# MCU.net
KiCad netlist of a schematic drawn in Altium Designer
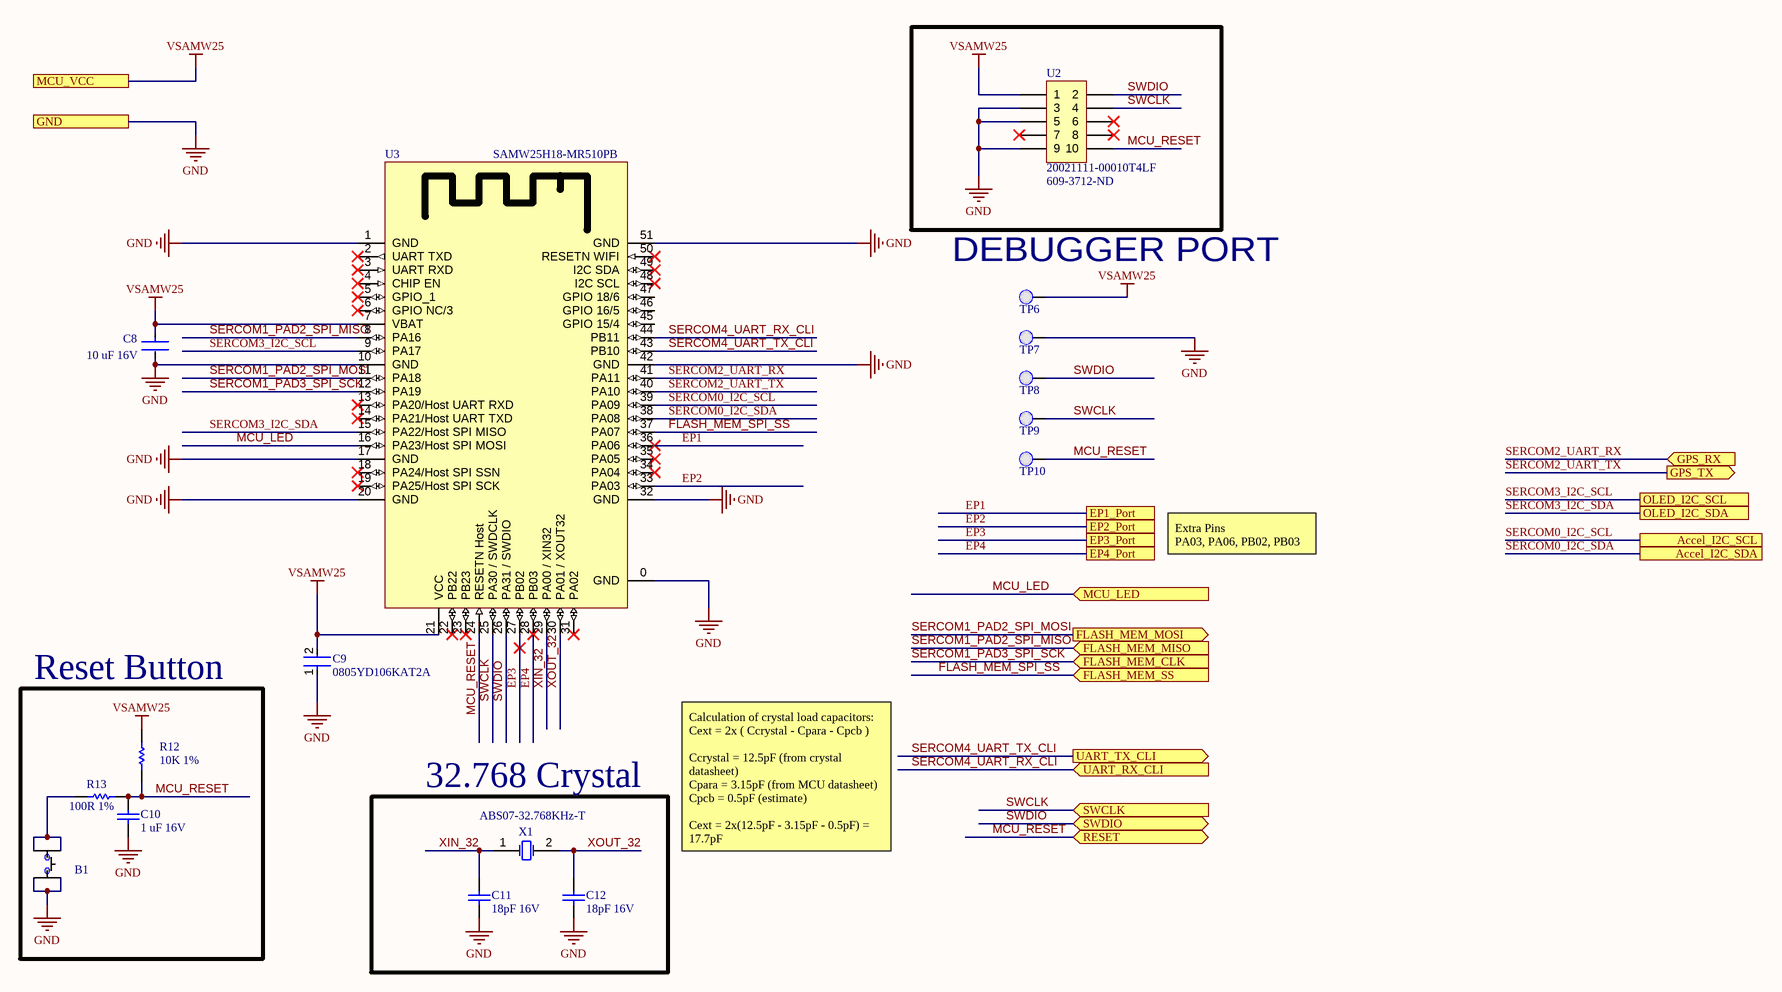
[diagram p0: MCU.SchDoc]

(export (version "E")
  (design (tool "Eeschema 10.0.6"))
  (components
    (comp (ref "B1")
      (value "PTS810 SJK 250 SMTR LFS")
      (footprint "PTS810 SJK 250 SMTR LFS")
      (description "SWITCH TACTILE SPST-NO 0.05A 16V Tactile Switch SPST-NO Top Actuated Surface Mount")
      (fields
        (field (name "MANUFACTURER") "ITT /  C&K Components")
        (field (name "MANUFACTURER PART NUMBER") "PTS810SJK250SMTRLFS")
      )
      (libsource (lib "Schematics") (part "PTS810 SJK 250 SMTR LFS"))
    )
    (comp (ref "C8")
      (value "10 uF 16V")
      (footprint "FP-0805-L_2_01_0_2-W_1_25-MFG")
      (description "General Purpose Ceramic Capacitor, 0805, 10uF, 10%, X5R, 15%, 16V")
      (fields (field (name "TOLERANCE") "10%") (field (name "VOLTAGE") "16V"))
      (libsource (lib "") (part "02cd4be3c70576c341d710602a673aa_1"))
    )
    (comp (ref "C9")
      (value "0805YD106KAT2A")
      (footprint "FP-0805-L_2_01_0_2-W_1_25-MFG")
      (description "General Purpose Ceramic Capacitor, 0805, 10uF, 10%, X5R, 15%, 16V")
      (fields (field (name "TOLERANCE") "10%") (field (name "VOLTAGE") "16V"))
      (libsource (lib "Altium Content Vault") (part "02cd4be3c70576c341d710602a673aa"))
    )
    (comp (ref "C10")
      (value "1 uF 16V")
      (footprint "CAPC1608X90X35ML15T15")
      (description "0603YC105JAT2A")
      (fields (field (name "MANUFACTURER") "AVX Interconnect / Elco"))
      (libsource (lib "Altium Content Vault") (part "CAP"))
    )
    (comp (ref "C11")
      (value "18pF 16V")
      (footprint "CAPC0603(1608)100_N")
      (description "CAP 18pF 16V ±5% 0603 (1608 Metric) Thickness 1mm SMD")
      (fields (field (name "TOLERANCE") "Â±5%"))
      (libsource (lib "Altium Content Vault") (part "CAP"))
    )
    (comp (ref "C12")
      (value "18pF 16V")
      (footprint "CAPC0603(1608)100_N")
      (description "CAP 18pF 16V ±5% 0603 (1608 Metric) Thickness 1mm SMD")
      (fields (field (name "TOLERANCE") "Â±5%"))
      (libsource (lib "Altium Content Vault") (part "CAP"))
    )
    (comp (ref "R12")
      (value "10K 1%")
      (footprint "RESC1609X55X30LL15T15")
      (description "Chip Resistor, 10 KOhm, +/- 1%, 0.1 W, -55 to 155 degC, 0603 (1608 Metric), RoHS, Tape and Reel")
      (fields (field (name "TOLERANCE") "1%") (field (name "MANUFACTURER") "Panasonic"))
      (libsource (lib "Altium Content Vault") (part "RES-2"))
    )
    (comp (ref "R13")
      (value "100R 1%")
      (footprint "RESC0603(1608)_N")
      (description "100R 0.1W 1% 0603 (1608 Metric)  SMD")
      (fields (field (name "TOLERANCE") "1 %") (field (name "POWER") "0.1 W"))
      (libsource (lib "Altium Content Vault") (part "RES"))
    )
    (comp (ref "TP6")
      (value "0.1\" Pad")
      (footprint "PCBComponent")
      (libsource (lib "Components - 12.02.20 - 18.05") (part "0.1{dblquote} Pad-A.4"))
    )
    (comp (ref "TP7")
      (value "0.1\" Pad")
      (footprint "PCBComponent")
      (libsource (lib "Components - 12.02.20 - 18.05") (part "0.1{dblquote} Pad-A.4"))
    )
    (comp (ref "TP8")
      (value "0.1\" Pad")
      (footprint "PCBComponent")
      (libsource (lib "Components - 12.02.20 - 18.05") (part "0.1{dblquote} Pad-A.4"))
    )
    (comp (ref "TP9")
      (value "0.1\" Pad")
      (footprint "PCBComponent")
      (libsource (lib "Components - 12.02.20 - 18.05") (part "0.1{dblquote} Pad-A.4"))
    )
    (comp (ref "TP10")
      (value "0.1\" Pad")
      (footprint "PCBComponent")
      (libsource (lib "Components - 12.02.20 - 18.05") (part "0.1{dblquote} Pad-A.4"))
    )
    (comp (ref "U2")
      (value "20021111-00010T4LF")
      (footprint "20021111-00010T4LF")
      (description "CONN HEADER 10POS UNSHD VERT T/H")
      (fields
        (field (name "MANUFACTURER") "Amphenol / FCI")
        (field (name "SUPPLIER PART NUMBER 1") "609-3712-ND")
      )
      (libsource (lib "Schematics") (part "20021111-00010T4LF"))
    )
    (comp (ref "U3")
      (value "SAMW25H18-MR510PB")
      (footprint "SAMW25H18-MR510PB")
      (description "RF TXRX MODULE WIFI TRACE ANT")
      (fields
        (field (name "MANUFACTURER") "Atmel")
        (field (name "MANUFACTURER PART NUMBER") "ATSAMW25H18-MR510PB")
      )
      (libsource (lib "Schematics") (part "SAMW25H18-MR510PB"))
    )
    (comp (ref "X1")
      (value "ABS07-32.768KHz-T")
      (footprint "ABRA-ABS07-2_V")
      (description "Crystal, 32.768 kHz, 12.5 pF, -40 to 85 degC, SMD Low Profile 3.2 x 1.5 x 0.9 mm, Tape and Reel")
      (fields (field (name "MANUFACTURER") "Abracon"))
      (libsource (lib "Altium Content Vault") (part "ABRA-ABS07-2"))
    )
  )
  (nets
    (net (code "2") (name "/EP1") (class "Default")
      (node (ref "U3") (pin "36") (pinfunction "PA06_36") (pintype "bidirectional+no_connect"))
    )
    (net (code "3") (name "/EP2") (class "Default")
      (node (ref "U3") (pin "33") (pinfunction "PA03_33") (pintype "bidirectional"))
    )
    (net (code "4") (name "/EP3") (class "Default")
      (node (ref "U3") (pin "27") (pinfunction "PB02_27") (pintype "bidirectional"))
    )
    (net (code "5") (name "/EP4") (class "Default")
      (node (ref "U3") (pin "28") (pinfunction "PB03_28") (pintype "bidirectional+no_connect"))
    )
    (net (code "6") (name "/FLASH_MEM_SPI_SS") (class "Default")
      (node (ref "U3") (pin "37") (pinfunction "PA07_37") (pintype "bidirectional"))
    )
    (net (code "7") (name "/MCU_LED") (class "Default")
      (node (ref "U3") (pin "16") (pinfunction "PA23/Host_SPI_MOSI_16") (pintype "bidirectional"))
    )
    (net (code "8") (name "/MCU_RESET") (class "Default")
      (node (ref "C10") (pin "2") (pinfunction "2_2") (pintype "passive"))
      (node (ref "R12") (pin "1") (pinfunction "1_1") (pintype "passive"))
      (node (ref "R13") (pin "2") (pinfunction "2_2") (pintype "passive"))
      (node (ref "TP10") (pin "1") (pinfunction "PAD_1") (pintype "passive"))
      (node (ref "U2") (pin "10") (pinfunction "10_10") (pintype "passive"))
      (node (ref "U3") (pin "24") (pinfunction "RESETN_Host_24") (pintype "input"))
    )
    (net (code "9") (name "/SERCOM0_I2C_SCL") (class "Default")
      (node (ref "U3") (pin "39") (pinfunction "PA09_39") (pintype "bidirectional"))
    )
    (net (code "10") (name "/SERCOM0_I2C_SDA") (class "Default")
      (node (ref "U3") (pin "38") (pinfunction "PA08_38") (pintype "bidirectional"))
    )
    (net (code "11") (name "/SERCOM1_PAD2_SPI_MISO") (class "Default")
      (node (ref "U3") (pin "8") (pinfunction "PA16_8") (pintype "bidirectional"))
    )
    (net (code "12") (name "/SERCOM1_PAD2_SPI_MOSI") (class "Default")
      (node (ref "U3") (pin "11") (pinfunction "PA18_11") (pintype "bidirectional"))
    )
    (net (code "13") (name "/SERCOM1_PAD3_SPI_SCK") (class "Default")
      (node (ref "U3") (pin "12") (pinfunction "PA19_12") (pintype "bidirectional"))
    )
    (net (code "14") (name "/SERCOM2_UART_RX") (class "Default")
      (node (ref "U3") (pin "41") (pinfunction "PA11_41") (pintype "bidirectional"))
    )
    (net (code "15") (name "/SERCOM2_UART_TX") (class "Default")
      (node (ref "U3") (pin "40") (pinfunction "PA10_40") (pintype "bidirectional"))
    )
    (net (code "16") (name "/SERCOM3_I2C_SCL") (class "Default")
      (node (ref "U3") (pin "9") (pinfunction "PA17_9") (pintype "bidirectional"))
    )
    (net (code "17") (name "/SERCOM3_I2C_SDA") (class "Default")
      (node (ref "U3") (pin "15") (pinfunction "PA22/Host_SPI_MISO_15") (pintype "bidirectional"))
    )
    (net (code "18") (name "/SERCOM4_UART_RX_CLI") (class "Default")
      (node (ref "U3") (pin "44") (pinfunction "PB11_44") (pintype "bidirectional"))
    )
    (net (code "19") (name "/SERCOM4_UART_TX_CLI") (class "Default")
      (node (ref "U3") (pin "43") (pinfunction "PB10_43") (pintype "bidirectional"))
    )
    (net (code "20") (name "/SWCLK") (class "Default")
      (node (ref "TP9") (pin "1") (pinfunction "PAD_1") (pintype "passive"))
      (node (ref "U2") (pin "4") (pinfunction "4_4") (pintype "passive"))
      (node (ref "U3") (pin "25") (pinfunction "PA30_/_SWDCLK_25") (pintype "bidirectional"))
    )
    (net (code "21") (name "/SWDIO") (class "Default")
      (node (ref "TP8") (pin "1") (pinfunction "PAD_1") (pintype "passive"))
      (node (ref "U2") (pin "2") (pinfunction "2_2") (pintype "passive"))
      (node (ref "U3") (pin "26") (pinfunction "PA31_/_SWDIO_26") (pintype "bidirectional"))
    )
    (net (code "22") (name "/XIN_32") (class "Default")
      (node (ref "C11") (pin "2") (pinfunction "2_2") (pintype "passive"))
      (node (ref "U3") (pin "29") (pinfunction "PA00_/_XIN32_29") (pintype "bidirectional"))
      (node (ref "X1") (pin "1") (pinfunction "X1_1") (pintype "passive"))
    )
    (net (code "23") (name "/XOUT_32") (class "Default")
      (node (ref "C12") (pin "2") (pinfunction "2_2") (pintype "passive"))
      (node (ref "U3") (pin "30") (pinfunction "PA01_/_XOUT32_30") (pintype "bidirectional"))
      (node (ref "X1") (pin "2") (pinfunction "X2_2") (pintype "passive"))
    )
    (net (code "24") (name "GND") (class "Default")
      (node (ref "B1") (pin "3") (pinfunction "3_3") (pintype "power_in"))
      (node (ref "B1") (pin "4") (pinfunction "4_4") (pintype "power_in"))
      (node (ref "C10") (pin "1") (pinfunction "1_1") (pintype "passive"))
      (node (ref "C11") (pin "1") (pinfunction "1_1") (pintype "passive"))
      (node (ref "C12") (pin "1") (pinfunction "1_1") (pintype "passive"))
      (node (ref "C8") (pin "2") (pinfunction "2_2") (pintype "passive"))
      (node (ref "C9") (pin "1") (pinfunction "1_1") (pintype "passive"))
      (node (ref "TP7") (pin "1") (pinfunction "PAD_1") (pintype "passive"))
      (node (ref "U2") (pin "3") (pinfunction "3_3") (pintype "passive"))
      (node (ref "U2") (pin "5") (pinfunction "5_5") (pintype "passive"))
      (node (ref "U2") (pin "9") (pinfunction "9_9") (pintype "passive"))
      (node (ref "U3") (pin "0") (pinfunction "GND_0") (pintype "power_in"))
      (node (ref "U3") (pin "1") (pinfunction "GND_1") (pintype "power_in"))
      (node (ref "U3") (pin "10") (pinfunction "GND_10") (pintype "power_in"))
      (node (ref "U3") (pin "17") (pinfunction "GND_17") (pintype "power_in"))
      (node (ref "U3") (pin "20") (pinfunction "GND_20") (pintype "power_in"))
      (node (ref "U3") (pin "32") (pinfunction "GND_32") (pintype "power_in"))
      (node (ref "U3") (pin "42") (pinfunction "GND_42") (pintype "power_in"))
      (node (ref "U3") (pin "51") (pinfunction "GND_51") (pintype "power_in"))
    )
    (net (code "25") (name "Net-(B1-Pad1)") (class "Default")
      (node (ref "B1") (pin "1") (pinfunction "1_1") (pintype "power_in"))
      (node (ref "B1") (pin "2") (pinfunction "2_2") (pintype "power_in"))
      (node (ref "R13") (pin "1") (pinfunction "1_1") (pintype "passive"))
    )
    (net (code "26") (name "VSAMW25") (class "Default")
      (node (ref "C8") (pin "1") (pinfunction "1_1") (pintype "passive"))
      (node (ref "C9") (pin "2") (pinfunction "2_2") (pintype "passive"))
      (node (ref "R12") (pin "2") (pinfunction "2_2") (pintype "passive"))
      (node (ref "TP6") (pin "1") (pinfunction "PAD_1") (pintype "passive"))
      (node (ref "U2") (pin "1") (pinfunction "1_1") (pintype "passive"))
      (node (ref "U3") (pin "21") (pinfunction "VCC_21") (pintype "power_in"))
      (node (ref "U3") (pin "7") (pinfunction "VBAT_7") (pintype "power_in"))
    )
    (net (code "27") (name "unconnected-(U2-Pad6)") (class "Default")
      (node (ref "U2") (pin "6") (pinfunction "6_6") (pintype "passive+no_connect"))
    )
    (net (code "28") (name "unconnected-(U2-Pad7)") (class "Default")
      (node (ref "U2") (pin "7") (pinfunction "7_7") (pintype "passive+no_connect"))
    )
    (net (code "29") (name "unconnected-(U2-Pad8)") (class "Default")
      (node (ref "U2") (pin "8") (pinfunction "8_8") (pintype "passive+no_connect"))
    )
    (net (code "30") (name "unconnected-(U3-CHIP_EN-Pad4)") (class "Default")
      (node (ref "U3") (pin "4") (pinfunction "CHIP_EN_4") (pintype "input+no_connect"))
    )
    (net (code "31") (name "unconnected-(U3-GPIO_1-Pad5)") (class "Default")
      (node (ref "U3") (pin "5") (pinfunction "GPIO_1_5") (pintype "bidirectional+no_connect"))
    )
    (net (code "32") (name "unconnected-(U3-GPIO_15{slash}4-Pad45)") (class "Default")
      (node (ref "U3") (pin "45") (pinfunction "GPIO_15/4_45") (pintype "bidirectional"))
    )
    (net (code "33") (name "unconnected-(U3-GPIO_16{slash}5-Pad46)") (class "Default")
      (node (ref "U3") (pin "46") (pinfunction "GPIO_16/5_46") (pintype "bidirectional"))
    )
    (net (code "34") (name "unconnected-(U3-GPIO_18{slash}6-Pad47)") (class "Default")
      (node (ref "U3") (pin "47") (pinfunction "GPIO_18/6_47") (pintype "bidirectional"))
    )
    (net (code "35") (name "unconnected-(U3-GPIO_NC{slash}3-Pad6)") (class "Default")
      (node (ref "U3") (pin "6") (pinfunction "GPIO_NC/3_6") (pintype "bidirectional+no_connect"))
    )
    (net (code "36") (name "unconnected-(U3-I2C_SCL-Pad48)") (class "Default")
      (node (ref "U3") (pin "48") (pinfunction "I2C_SCL_48") (pintype "bidirectional+no_connect"))
    )
    (net (code "37") (name "unconnected-(U3-I2C_SDA-Pad49)") (class "Default")
      (node (ref "U3") (pin "49") (pinfunction "I2C_SDA_49") (pintype "bidirectional+no_connect"))
    )
    (net (code "38") (name "unconnected-(U3-PA02-Pad31)") (class "Default")
      (node (ref "U3") (pin "31") (pinfunction "PA02_31") (pintype "bidirectional+no_connect"))
    )
    (net (code "39") (name "unconnected-(U3-PA04-Pad34)") (class "Default")
      (node (ref "U3") (pin "34") (pinfunction "PA04_34") (pintype "bidirectional+no_connect"))
    )
    (net (code "40") (name "unconnected-(U3-PA05-Pad35)") (class "Default")
      (node (ref "U3") (pin "35") (pinfunction "PA05_35") (pintype "bidirectional+no_connect"))
    )
    (net (code "41") (name "unconnected-(U3-PA20{slash}Host_UART_RXD-Pad13)") (class "Default")
      (node (ref "U3") (pin "13") (pinfunction "PA20/Host_UART_RXD_13") (pintype "bidirectional+no_connect"))
    )
    (net (code "42") (name "unconnected-(U3-PA21{slash}Host_UART_TXD-Pad14)") (class "Default")
      (node (ref "U3") (pin "14") (pinfunction "PA21/Host_UART_TXD_14") (pintype "bidirectional+no_connect"))
    )
    (net (code "43") (name "unconnected-(U3-PA24{slash}Host_SPI_SSN-Pad18)") (class "Default")
      (node (ref "U3") (pin "18") (pinfunction "PA24/Host_SPI_SSN_18") (pintype "bidirectional+no_connect"))
    )
    (net (code "44") (name "unconnected-(U3-PA25{slash}Host_SPI_SCK-Pad19)") (class "Default")
      (node (ref "U3") (pin "19") (pinfunction "PA25/Host_SPI_SCK_19") (pintype "bidirectional+no_connect"))
    )
    (net (code "45") (name "unconnected-(U3-PB22-Pad22)") (class "Default")
      (node (ref "U3") (pin "22") (pinfunction "PB22_22") (pintype "bidirectional+no_connect"))
    )
    (net (code "46") (name "unconnected-(U3-PB23-Pad23)") (class "Default")
      (node (ref "U3") (pin "23") (pinfunction "PB23_23") (pintype "bidirectional+no_connect"))
    )
    (net (code "47") (name "unconnected-(U3-RESETN_WIFI-Pad50)") (class "Default")
      (node (ref "U3") (pin "50") (pinfunction "RESETN_WIFI_50") (pintype "input+no_connect"))
    )
    (net (code "48") (name "unconnected-(U3-UART_RXD-Pad3)") (class "Default")
      (node (ref "U3") (pin "3") (pinfunction "UART_RXD_3") (pintype "input+no_connect"))
    )
    (net (code "49") (name "unconnected-(U3-UART_TXD-Pad2)") (class "Default")
      (node (ref "U3") (pin "2") (pinfunction "UART_TXD_2") (pintype "output+no_connect"))
    )
  )
)
